# minimum_system.net
KiCad netlist of a schematic drawn in EAGLE
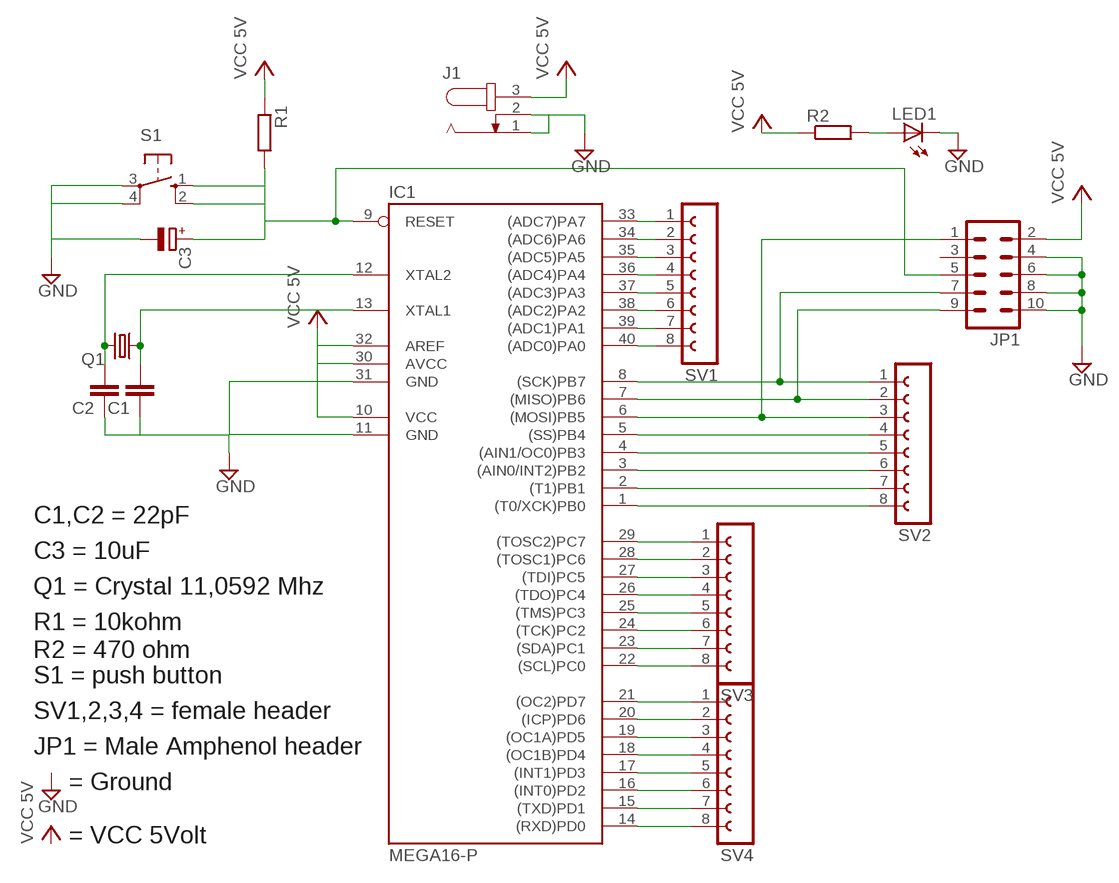
[diagram p0: schematic, sheet 1]

(export (version "E")
  (design (tool "Eeschema 10.0.6"))
  (components
    (comp (ref "C1")
      (value "C2.5/2")
      (footprint "eagle-import:C2.5-2")
      (libsource (lib "eagle-import") (part "C2.5/2"))
    )
    (comp (ref "C2")
      (value "C2.5/2")
      (footprint "eagle-import:C2.5-2")
      (libsource (lib "eagle-import") (part "C2.5/2"))
    )
    (comp (ref "C3")
      (value "CPOL-EUE3.5-8")
      (footprint "eagle-import:E3,5-8")
      (libsource (lib "eagle-import") (part "CPOL-EUE3.5-8"))
    )
    (comp (ref "IC1")
      (value "MEGA16-P")
      (footprint "eagle-import:DIL40")
      (libsource (lib "eagle-import") (part "MEGA16-P"))
    )
    (comp (ref "J1")
      (value "JACK-PLUG0")
      (footprint "eagle-import:SPC4077")
      (libsource (lib "eagle-import") (part "JACK-PLUG0"))
    )
    (comp (ref "JP1")
      (value "ML10")
      (footprint "eagle-import:ML10")
      (libsource (lib "eagle-import") (part "ML10"))
    )
    (comp (ref "LED1")
      (value "LED5MM")
      (footprint "eagle-import:LED5MM")
      (libsource (lib "eagle-import") (part "LED5MM"))
    )
    (comp (ref "Q1")
      (value "CRYSTALHC49S")
      (footprint "eagle-import:HC49_S")
      (libsource (lib "eagle-import") (part "CRYSTALHC49S"))
    )
    (comp (ref "R1")
      (value "R-EU_0207/10")
      (footprint "eagle-import:0207_10")
      (libsource (lib "eagle-import") (part "R-EU_0207/10"))
    )
    (comp (ref "R2")
      (value "R-EU_0207/10")
      (footprint "eagle-import:0207_10")
      (libsource (lib "eagle-import") (part "R-EU_0207/10"))
    )
    (comp (ref "S1")
      (value "10-XX")
      (footprint "eagle-import:B3F-10XX")
      (libsource (lib "eagle-import") (part "10-XX"))
    )
    (comp (ref "SV1")
      (value "FE08-1")
      (footprint "eagle-import:FE08")
      (libsource (lib "eagle-import") (part "FE08-1"))
    )
    (comp (ref "SV2")
      (value "FE08-1")
      (footprint "eagle-import:FE08")
      (libsource (lib "eagle-import") (part "FE08-1"))
    )
    (comp (ref "SV3")
      (value "FE08-1")
      (footprint "eagle-import:FE08")
      (libsource (lib "eagle-import") (part "FE08-1"))
    )
    (comp (ref "SV4")
      (value "FE08-1")
      (footprint "eagle-import:FE08")
      (libsource (lib "eagle-import") (part "FE08-1"))
    )
  )
  (nets
    (net (code "1") (name "GND") (class "Default")
      (node (ref "C1") (pin "1") (pinfunction "1_1") (pintype "passive"))
      (node (ref "C2") (pin "1") (pinfunction "1_1") (pintype "passive"))
      (node (ref "C3") (pin "-") (pinfunction "-_-") (pintype "passive"))
      (node (ref "IC1") (pin "11") (pinfunction "GND_11") (pintype "power_in"))
      (node (ref "IC1") (pin "31") (pinfunction "GND_31") (pintype "power_in"))
      (node (ref "J1") (pin "1") (pinfunction "1_1") (pintype "passive"))
      (node (ref "J1") (pin "2") (pinfunction "2_2") (pintype "passive"))
      (node (ref "JP1") (pin "10") (pinfunction "10_10") (pintype "passive"))
      (node (ref "JP1") (pin "4") (pinfunction "4_4") (pintype "passive"))
      (node (ref "JP1") (pin "6") (pinfunction "6_6") (pintype "passive"))
      (node (ref "JP1") (pin "8") (pinfunction "8_8") (pintype "passive"))
      (node (ref "LED1") (pin "K") (pinfunction "C_K") (pintype "passive"))
      (node (ref "S1") (pin "3") (pinfunction "P_3") (pintype "passive"))
      (node (ref "S1") (pin "4") (pinfunction "P1_4") (pintype "passive"))
    )
    (net (code "2") (name "Net-(IC1-(ADC0)PA0)") (class "Default")
      (node (ref "IC1") (pin "40") (pinfunction "(ADC0)PA0_40") (pintype "bidirectional"))
      (node (ref "SV1") (pin "8") (pinfunction "8_8") (pintype "passive"))
    )
    (net (code "3") (name "Net-(IC1-(ADC1)PA1)") (class "Default")
      (node (ref "IC1") (pin "39") (pinfunction "(ADC1)PA1_39") (pintype "bidirectional"))
      (node (ref "SV1") (pin "7") (pinfunction "7_7") (pintype "passive"))
    )
    (net (code "4") (name "Net-(IC1-(ADC2)PA2)") (class "Default")
      (node (ref "IC1") (pin "38") (pinfunction "(ADC2)PA2_38") (pintype "bidirectional"))
      (node (ref "SV1") (pin "6") (pinfunction "6_6") (pintype "passive"))
    )
    (net (code "5") (name "Net-(IC1-(ADC3)PA3)") (class "Default")
      (node (ref "IC1") (pin "37") (pinfunction "(ADC3)PA3_37") (pintype "bidirectional"))
      (node (ref "SV1") (pin "5") (pinfunction "5_5") (pintype "passive"))
    )
    (net (code "6") (name "Net-(IC1-(ADC4)PA4)") (class "Default")
      (node (ref "IC1") (pin "36") (pinfunction "(ADC4)PA4_36") (pintype "bidirectional"))
      (node (ref "SV1") (pin "4") (pinfunction "4_4") (pintype "passive"))
    )
    (net (code "7") (name "Net-(IC1-(ADC5)PA5)") (class "Default")
      (node (ref "IC1") (pin "35") (pinfunction "(ADC5)PA5_35") (pintype "bidirectional"))
      (node (ref "SV1") (pin "3") (pinfunction "3_3") (pintype "passive"))
    )
    (net (code "8") (name "Net-(IC1-(ADC6)PA6)") (class "Default")
      (node (ref "IC1") (pin "34") (pinfunction "(ADC6)PA6_34") (pintype "bidirectional"))
      (node (ref "SV1") (pin "2") (pinfunction "2_2") (pintype "passive"))
    )
    (net (code "9") (name "Net-(IC1-(ADC7)PA7)") (class "Default")
      (node (ref "IC1") (pin "33") (pinfunction "(ADC7)PA7_33") (pintype "bidirectional"))
      (node (ref "SV1") (pin "1") (pinfunction "1_1") (pintype "passive"))
    )
    (net (code "10") (name "Net-(IC1-(AIN0{slash}INT2)PB2)") (class "Default")
      (node (ref "IC1") (pin "3") (pinfunction "(AIN0/INT2)PB2_3") (pintype "bidirectional"))
      (node (ref "SV2") (pin "6") (pinfunction "6_6") (pintype "passive"))
    )
    (net (code "11") (name "Net-(IC1-(AIN1{slash}OC0)PB3)") (class "Default")
      (node (ref "IC1") (pin "4") (pinfunction "(AIN1/OC0)PB3_4") (pintype "bidirectional"))
      (node (ref "SV2") (pin "5") (pinfunction "5_5") (pintype "passive"))
    )
    (net (code "12") (name "Net-(IC1-(ICP)PD6)") (class "Default")
      (node (ref "IC1") (pin "20") (pinfunction "(ICP)PD6_20") (pintype "bidirectional"))
      (node (ref "SV4") (pin "2") (pinfunction "2_2") (pintype "passive"))
    )
    (net (code "13") (name "Net-(IC1-(INT0)PD2)") (class "Default")
      (node (ref "IC1") (pin "16") (pinfunction "(INT0)PD2_16") (pintype "bidirectional"))
      (node (ref "SV4") (pin "6") (pinfunction "6_6") (pintype "passive"))
    )
    (net (code "14") (name "Net-(IC1-(INT1)PD3)") (class "Default")
      (node (ref "IC1") (pin "17") (pinfunction "(INT1)PD3_17") (pintype "bidirectional"))
      (node (ref "SV4") (pin "5") (pinfunction "5_5") (pintype "passive"))
    )
    (net (code "15") (name "Net-(IC1-(MISO)PB6)") (class "Default")
      (node (ref "IC1") (pin "7") (pinfunction "(MISO)PB6_7") (pintype "bidirectional"))
      (node (ref "JP1") (pin "9") (pinfunction "9_9") (pintype "passive"))
      (node (ref "SV2") (pin "2") (pinfunction "2_2") (pintype "passive"))
    )
    (net (code "16") (name "Net-(IC1-(MOSI)PB5)") (class "Default")
      (node (ref "IC1") (pin "6") (pinfunction "(MOSI)PB5_6") (pintype "bidirectional"))
      (node (ref "JP1") (pin "1") (pinfunction "1_1") (pintype "passive"))
      (node (ref "SV2") (pin "3") (pinfunction "3_3") (pintype "passive"))
    )
    (net (code "17") (name "Net-(IC1-(OC1A)PD5)") (class "Default")
      (node (ref "IC1") (pin "19") (pinfunction "(OC1A)PD5_19") (pintype "bidirectional"))
      (node (ref "SV4") (pin "3") (pinfunction "3_3") (pintype "passive"))
    )
    (net (code "18") (name "Net-(IC1-(OC1B)PD4)") (class "Default")
      (node (ref "IC1") (pin "18") (pinfunction "(OC1B)PD4_18") (pintype "bidirectional"))
      (node (ref "SV4") (pin "4") (pinfunction "4_4") (pintype "passive"))
    )
    (net (code "19") (name "Net-(IC1-(OC2)PD7)") (class "Default")
      (node (ref "IC1") (pin "21") (pinfunction "(OC2)PD7_21") (pintype "bidirectional"))
      (node (ref "SV4") (pin "1") (pinfunction "1_1") (pintype "passive"))
    )
    (net (code "20") (name "Net-(IC1-(RXD)PD0)") (class "Default")
      (node (ref "IC1") (pin "14") (pinfunction "(RXD)PD0_14") (pintype "bidirectional"))
      (node (ref "SV4") (pin "8") (pinfunction "8_8") (pintype "passive"))
    )
    (net (code "21") (name "Net-(IC1-(SCK)PB7)") (class "Default")
      (node (ref "IC1") (pin "8") (pinfunction "(SCK)PB7_8") (pintype "bidirectional"))
      (node (ref "JP1") (pin "7") (pinfunction "7_7") (pintype "passive"))
      (node (ref "SV2") (pin "1") (pinfunction "1_1") (pintype "passive"))
    )
    (net (code "22") (name "Net-(IC1-(SCL)PC0)") (class "Default")
      (node (ref "IC1") (pin "22") (pinfunction "(SCL)PC0_22") (pintype "bidirectional"))
      (node (ref "SV3") (pin "8") (pinfunction "8_8") (pintype "passive"))
    )
    (net (code "23") (name "Net-(IC1-(SDA)PC1)") (class "Default")
      (node (ref "IC1") (pin "23") (pinfunction "(SDA)PC1_23") (pintype "bidirectional"))
      (node (ref "SV3") (pin "7") (pinfunction "7_7") (pintype "passive"))
    )
    (net (code "24") (name "Net-(IC1-(SS)PB4)") (class "Default")
      (node (ref "IC1") (pin "5") (pinfunction "(SS)PB4_5") (pintype "bidirectional"))
      (node (ref "SV2") (pin "4") (pinfunction "4_4") (pintype "passive"))
    )
    (net (code "25") (name "Net-(IC1-(T0{slash}XCK)PB0)") (class "Default")
      (node (ref "IC1") (pin "1") (pinfunction "(T0/XCK)PB0_1") (pintype "bidirectional"))
      (node (ref "SV2") (pin "8") (pinfunction "8_8") (pintype "passive"))
    )
    (net (code "26") (name "Net-(IC1-(T1)PB1)") (class "Default")
      (node (ref "IC1") (pin "2") (pinfunction "(T1)PB1_2") (pintype "bidirectional"))
      (node (ref "SV2") (pin "7") (pinfunction "7_7") (pintype "passive"))
    )
    (net (code "27") (name "Net-(IC1-(TCK)PC2)") (class "Default")
      (node (ref "IC1") (pin "24") (pinfunction "(TCK)PC2_24") (pintype "bidirectional"))
      (node (ref "SV3") (pin "6") (pinfunction "6_6") (pintype "passive"))
    )
    (net (code "28") (name "Net-(IC1-(TDI)PC5)") (class "Default")
      (node (ref "IC1") (pin "27") (pinfunction "(TDI)PC5_27") (pintype "bidirectional"))
      (node (ref "SV3") (pin "3") (pinfunction "3_3") (pintype "passive"))
    )
    (net (code "29") (name "Net-(IC1-(TDO)PC4)") (class "Default")
      (node (ref "IC1") (pin "26") (pinfunction "(TDO)PC4_26") (pintype "bidirectional"))
      (node (ref "SV3") (pin "4") (pinfunction "4_4") (pintype "passive"))
    )
    (net (code "30") (name "Net-(IC1-(TMS)PC3)") (class "Default")
      (node (ref "IC1") (pin "25") (pinfunction "(TMS)PC3_25") (pintype "bidirectional"))
      (node (ref "SV3") (pin "5") (pinfunction "5_5") (pintype "passive"))
    )
    (net (code "31") (name "Net-(IC1-(TOSC1)PC6)") (class "Default")
      (node (ref "IC1") (pin "28") (pinfunction "(TOSC1)PC6_28") (pintype "bidirectional"))
      (node (ref "SV3") (pin "2") (pinfunction "2_2") (pintype "passive"))
    )
    (net (code "32") (name "Net-(IC1-(TOSC2)PC7)") (class "Default")
      (node (ref "IC1") (pin "29") (pinfunction "(TOSC2)PC7_29") (pintype "bidirectional"))
      (node (ref "SV3") (pin "1") (pinfunction "1_1") (pintype "passive"))
    )
    (net (code "33") (name "Net-(IC1-(TXD)PD1)") (class "Default")
      (node (ref "IC1") (pin "15") (pinfunction "(TXD)PD1_15") (pintype "bidirectional"))
      (node (ref "SV4") (pin "7") (pinfunction "7_7") (pintype "passive"))
    )
    (net (code "34") (name "Net-(IC1-RESET)") (class "Default")
      (node (ref "IC1") (pin "9") (pinfunction "RESET_9") (pintype "input"))
      (node (ref "JP1") (pin "5") (pinfunction "5_5") (pintype "passive"))
    )
    (net (code "35") (name "Net-(IC1-XTAL1)") (class "Default")
      (node (ref "C1") (pin "2") (pinfunction "2_2") (pintype "passive"))
      (node (ref "IC1") (pin "13") (pinfunction "XTAL1_13") (pintype "bidirectional"))
      (node (ref "Q1") (pin "1") (pinfunction "1_1") (pintype "passive"))
    )
    (net (code "36") (name "Net-(IC1-XTAL2)") (class "Default")
      (node (ref "C2") (pin "2") (pinfunction "2_2") (pintype "passive"))
      (node (ref "IC1") (pin "12") (pinfunction "XTAL2_12") (pintype "bidirectional"))
      (node (ref "Q1") (pin "2") (pinfunction "2_2") (pintype "passive"))
    )
    (net (code "37") (name "Net-(LED1-PadA)") (class "Default")
      (node (ref "LED1") (pin "A") (pinfunction "A_A") (pintype "passive"))
      (node (ref "R2") (pin "2") (pinfunction "2_2") (pintype "passive"))
    )
    (net (code "38") (name "Net-(S1-S)") (class "Default")
      (node (ref "C3") (pin "+") (pinfunction "+_+") (pintype "passive"))
      (node (ref "R1") (pin "2") (pinfunction "2_2") (pintype "passive"))
      (node (ref "S1") (pin "1") (pinfunction "S_1") (pintype "passive"))
      (node (ref "S1") (pin "2") (pinfunction "S1_2") (pintype "passive"))
    )
    (net (code "39") (name "VCC 5V") (class "Default")
      (node (ref "IC1") (pin "10") (pinfunction "VCC_10") (pintype "power_in"))
      (node (ref "IC1") (pin "30") (pinfunction "AVCC_30") (pintype "power_in"))
      (node (ref "IC1") (pin "32") (pinfunction "AREF_32") (pintype "passive"))
      (node (ref "J1") (pin "3") (pinfunction "3_3") (pintype "passive"))
      (node (ref "JP1") (pin "2") (pinfunction "2_2") (pintype "passive"))
      (node (ref "R1") (pin "1") (pinfunction "1_1") (pintype "passive"))
      (node (ref "R2") (pin "1") (pinfunction "1_1") (pintype "passive"))
    )
    (net (code "40") (name "unconnected-(JP1-Pad3)") (class "Default")
      (node (ref "JP1") (pin "3") (pinfunction "3_3") (pintype "passive"))
    )
  )
)
